# DVT-Notch-Filter.net
KiCad netlist of a schematic drawn in Altium Designer
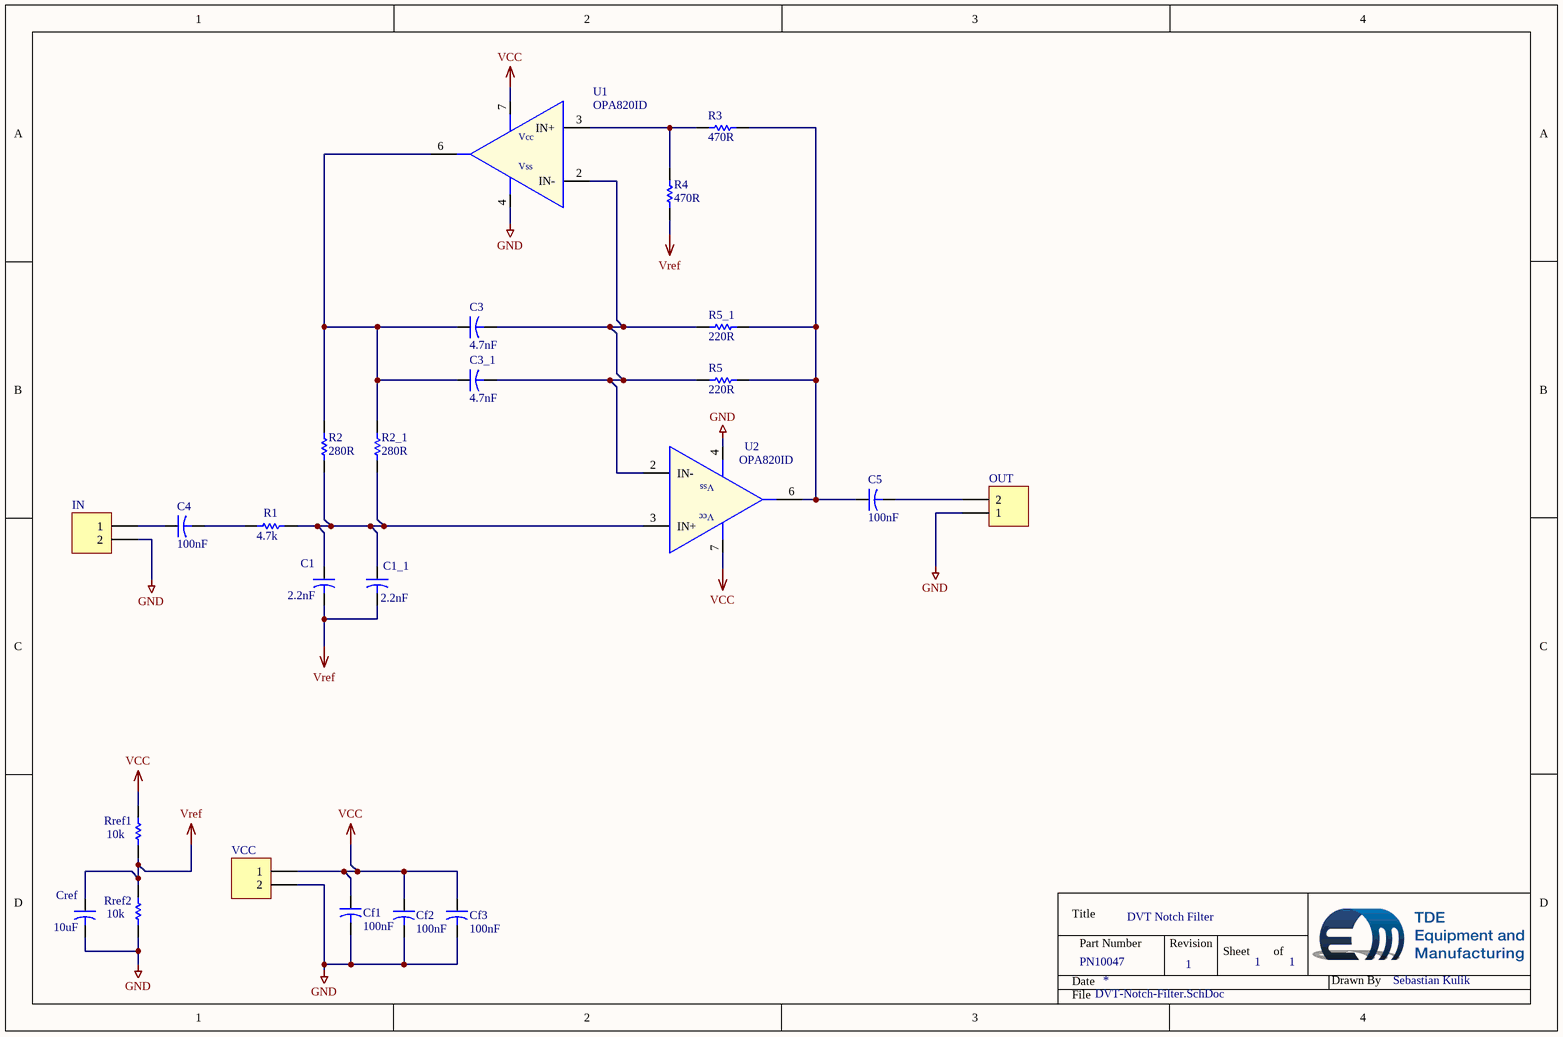
[diagram p0: DVT-Notch-Filter.SchDoc]

(export (version "E")
  (design (tool "Eeschema 10.0.6"))
  (components
    (comp (ref "*") (value "Eye") (footprint "Eye") (libsource (lib "ICs") (part "Eye")))
    (comp (ref "-") (value "Eye") (footprint "Eye") (libsource (lib "ICs") (part "Eye")))
    (comp (ref "C1")
      (value "2.2nF")
      (footprint "Dummy-10mm")
      (description "Capacitor-Dummy-THT")
      (fields (field (name "PUBLISHER") "Sebastian Kulik"))
      (libsource (lib "Capacitors") (part "Capacitor-Dummy-THT"))
    )
    (comp (ref "C1_1")
      (value "2.2nF")
      (footprint "Dummy-10mm")
      (description "Capacitor-Dummy-THT")
      (fields (field (name "PUBLISHER") "Sebastian Kulik"))
      (libsource (lib "Capacitors") (part "Capacitor-Dummy-THT"))
    )
    (comp (ref "C3")
      (value "4.7nF")
      (footprint "Dummy-10mm")
      (description "Capacitor-Dummy-THT")
      (fields (field (name "PUBLISHER") "Sebastian Kulik"))
      (libsource (lib "Capacitors") (part "Capacitor-Dummy-THT"))
    )
    (comp (ref "C3_1")
      (value "4.7nF")
      (footprint "Dummy-10mm")
      (description "Capacitor-Dummy-THT")
      (fields (field (name "PUBLISHER") "Sebastian Kulik"))
      (libsource (lib "Capacitors") (part "Capacitor-Dummy-THT"))
    )
    (comp (ref "C4")
      (value "100nF")
      (footprint "Dummy-10mm")
      (description "Capacitor-Dummy-THT")
      (fields (field (name "PUBLISHER") "Sebastian Kulik"))
      (libsource (lib "Capacitors") (part "Capacitor-Dummy-THT"))
    )
    (comp (ref "C5")
      (value "100nF")
      (footprint "Dummy-10mm")
      (description "Capacitor-Dummy-THT")
      (fields (field (name "PUBLISHER") "Sebastian Kulik"))
      (libsource (lib "Capacitors") (part "Capacitor-Dummy-THT"))
    )
    (comp (ref "Cf1")
      (value "100nF")
      (footprint "Dummy-10mm")
      (description "Capacitor-Dummy-THT")
      (fields (field (name "PUBLISHER") "Sebastian Kulik"))
      (libsource (lib "Capacitors") (part "Capacitor-Dummy-THT"))
    )
    (comp (ref "Cf2")
      (value "100nF")
      (footprint "Dummy-10mm")
      (description "Capacitor-Dummy-THT")
      (fields (field (name "PUBLISHER") "Sebastian Kulik"))
      (libsource (lib "Capacitors") (part "Capacitor-Dummy-THT"))
    )
    (comp (ref "Cf3")
      (value "100nF")
      (footprint "Dummy-10mm")
      (description "Capacitor-Dummy-THT")
      (fields (field (name "PUBLISHER") "Sebastian Kulik"))
      (libsource (lib "Capacitors") (part "Capacitor-Dummy-THT"))
    )
    (comp (ref "Cref")
      (value "10uF")
      (footprint "Dummy-10mm")
      (description "Capacitor-Dummy-THT")
      (fields (field (name "PUBLISHER") "Sebastian Kulik"))
      (libsource (lib "Capacitors") (part "Capacitor-Dummy-THT"))
    )
    (comp (ref "IN")
      (value "PHOENIX_1715721")
      (footprint "Phoenix-2-5_08")
      (description "Phoenix, 2 pol, 5.08mm, 22A, 715721")
      (fields (field (name "MANUFACTURER") "Phoenix") (field (name "PUBLISHER") "Sebastian Kulik"))
      (libsource (lib "Connectors") (part "2Pol_1715721"))
    )
    (comp (ref "OUT")
      (value "PHOENIX_1715721")
      (footprint "Phoenix-2-5_08")
      (description "Phoenix, 2 pol, 5.08mm, 22A, 715721")
      (fields (field (name "MANUFACTURER") "Phoenix") (field (name "PUBLISHER") "Sebastian Kulik"))
      (libsource (lib "") (part "2Pol_1715721_1"))
    )
    (comp (ref "R1")
      (value "4.7k")
      (footprint "Dummy-10mm")
      (description "Resistor-Dummy-THT")
      (fields (field (name "PUBLISHER") "Sebastian Kulik"))
      (libsource (lib "Resistors") (part "Resistor-Dummy-THT"))
    )
    (comp (ref "R2")
      (value "280R")
      (footprint "Dummy-10mm")
      (description "Resistor-Dummy-THT")
      (fields (field (name "PUBLISHER") "Sebastian Kulik"))
      (libsource (lib "Resistors") (part "Resistor-Dummy-THT"))
    )
    (comp (ref "R2_1")
      (value "280R")
      (footprint "Dummy-10mm")
      (description "Resistor-Dummy-THT")
      (fields (field (name "PUBLISHER") "Sebastian Kulik"))
      (libsource (lib "Resistors") (part "Resistor-Dummy-THT"))
    )
    (comp (ref "R3")
      (value "470R")
      (footprint "Dummy-10mm")
      (description "Resistor-Dummy-THT")
      (fields (field (name "PUBLISHER") "Sebastian Kulik"))
      (libsource (lib "Resistors") (part "Resistor-Dummy-THT"))
    )
    (comp (ref "R4")
      (value "470R")
      (footprint "Dummy-10mm")
      (description "Resistor-Dummy-THT")
      (fields (field (name "PUBLISHER") "Sebastian Kulik"))
      (libsource (lib "Resistors") (part "Resistor-Dummy-THT"))
    )
    (comp (ref "R5")
      (value "220R")
      (footprint "Dummy-10mm")
      (description "Resistor-Dummy-THT")
      (fields (field (name "PUBLISHER") "Sebastian Kulik"))
      (libsource (lib "Resistors") (part "Resistor-Dummy-THT"))
    )
    (comp (ref "R5_1")
      (value "220R")
      (footprint "Dummy-10mm")
      (description "Resistor-Dummy-THT")
      (fields (field (name "PUBLISHER") "Sebastian Kulik"))
      (libsource (lib "Resistors") (part "Resistor-Dummy-THT"))
    )
    (comp (ref "Rref1")
      (value "10k")
      (footprint "Dummy-10mm")
      (description "Resistor-Dummy-THT")
      (fields (field (name "PUBLISHER") "Sebastian Kulik"))
      (libsource (lib "Resistors") (part "Resistor-Dummy-THT"))
    )
    (comp (ref "Rref2")
      (value "10k")
      (footprint "Dummy-10mm")
      (description "Resistor-Dummy-THT")
      (fields (field (name "PUBLISHER") "Sebastian Kulik"))
      (libsource (lib "Resistors") (part "Resistor-Dummy-THT"))
    )
    (comp (ref "U1")
      (value "OPA820ID")
      (footprint "SOP8_L")
      (description "High speed OP, 260MHz")
      (fields (field (name "MANUFACTURER") "TI") (field (name "PUBLISHER") "Sebastian Kulik"))
      (libsource (lib "ICs") (part "OPA820ID"))
    )
    (comp (ref "U2")
      (value "OPA820ID")
      (footprint "SOP8_L")
      (description "High speed OP, 260MHz")
      (fields (field (name "MANUFACTURER") "TI") (field (name "PUBLISHER") "Sebastian Kulik"))
      (libsource (lib "") (part "OPA820ID_1"))
    )
    (comp (ref "VCC")
      (value "PHOENIX_1715721")
      (footprint "Phoenix-2-5_08")
      (description "Phoenix, 2 pol, 5.08mm, 22A, 715721")
      (fields (field (name "MANUFACTURER") "Phoenix") (field (name "PUBLISHER") "Sebastian Kulik"))
      (libsource (lib "Connectors") (part "2Pol_1715721"))
    )
  )
  (nets
    (net (code "1") (name "GND") (class "Default")
      (node (ref "Cf1") (pin "2") (pinfunction "2_2") (pintype "passive"))
      (node (ref "Cf2") (pin "2") (pinfunction "2_2") (pintype "passive"))
      (node (ref "Cf3") (pin "2") (pinfunction "2_2") (pintype "passive"))
      (node (ref "Cref") (pin "2") (pinfunction "2_2") (pintype "passive"))
      (node (ref "IN") (pin "2") (pinfunction "2_2") (pintype "passive"))
      (node (ref "OUT") (pin "1") (pinfunction "1_1") (pintype "passive"))
      (node (ref "Rref2") (pin "1") (pinfunction "1_1") (pintype "passive"))
      (node (ref "U1") (pin "4") (pinfunction "Vss_4") (pintype "passive"))
      (node (ref "U2") (pin "4") (pinfunction "Vss_4") (pintype "passive"))
      (node (ref "VCC") (pin "2") (pinfunction "2_2") (pintype "passive"))
    )
    (net (code "2") (name "Net-(C4-Pad1)") (class "Default")
      (node (ref "C4") (pin "1") (pinfunction "1_1") (pintype "passive"))
      (node (ref "IN") (pin "1") (pinfunction "1_1") (pintype "passive"))
    )
    (net (code "3") (name "Net-(C4-Pad2)") (class "Default")
      (node (ref "C4") (pin "2") (pinfunction "2_2") (pintype "passive"))
      (node (ref "R1") (pin "2") (pinfunction "2_2") (pintype "passive"))
    )
    (net (code "4") (name "Net-(C5-Pad2)") (class "Default")
      (node (ref "C5") (pin "2") (pinfunction "2_2") (pintype "passive"))
      (node (ref "OUT") (pin "2") (pinfunction "2_2") (pintype "passive"))
    )
    (net (code "5") (name "Net-(U1-IN+)") (class "Default")
      (node (ref "R3") (pin "2") (pinfunction "2_2") (pintype "passive"))
      (node (ref "R4") (pin "2") (pinfunction "2_2") (pintype "passive"))
      (node (ref "U1") (pin "3") (pinfunction "IN+_3") (pintype "power_in"))
    )
    (net (code "6") (name "Net-(U1-IN-)") (class "Default")
      (node (ref "C3") (pin "2") (pinfunction "2_2") (pintype "passive"))
      (node (ref "C3_1") (pin "2") (pinfunction "2_2") (pintype "passive"))
      (node (ref "R5") (pin "1") (pinfunction "1_1") (pintype "passive"))
      (node (ref "R5_1") (pin "1") (pinfunction "1_1") (pintype "passive"))
      (node (ref "U1") (pin "2") (pinfunction "IN-_2") (pintype "passive"))
      (node (ref "U2") (pin "2") (pinfunction "IN-_2") (pintype "passive"))
    )
    (net (code "7") (name "Net-(U1-OUT)") (class "Default")
      (node (ref "C3") (pin "1") (pinfunction "1_1") (pintype "passive"))
      (node (ref "C3_1") (pin "1") (pinfunction "1_1") (pintype "passive"))
      (node (ref "R2") (pin "1") (pinfunction "1_1") (pintype "passive"))
      (node (ref "R2_1") (pin "1") (pinfunction "1_1") (pintype "passive"))
      (node (ref "U1") (pin "6") (pinfunction "OUT_6") (pintype "passive"))
    )
    (net (code "8") (name "Net-(U2-IN+)") (class "Default")
      (node (ref "C1") (pin "1") (pinfunction "1_1") (pintype "passive"))
      (node (ref "C1_1") (pin "1") (pinfunction "1_1") (pintype "passive"))
      (node (ref "R1") (pin "1") (pinfunction "1_1") (pintype "passive"))
      (node (ref "R2") (pin "2") (pinfunction "2_2") (pintype "passive"))
      (node (ref "R2_1") (pin "2") (pinfunction "2_2") (pintype "passive"))
      (node (ref "U2") (pin "3") (pinfunction "IN+_3") (pintype "power_in"))
    )
    (net (code "9") (name "Net-(U2-OUT)") (class "Default")
      (node (ref "C5") (pin "1") (pinfunction "1_1") (pintype "passive"))
      (node (ref "R3") (pin "1") (pinfunction "1_1") (pintype "passive"))
      (node (ref "R5") (pin "2") (pinfunction "2_2") (pintype "passive"))
      (node (ref "R5_1") (pin "2") (pinfunction "2_2") (pintype "passive"))
      (node (ref "U2") (pin "6") (pinfunction "OUT_6") (pintype "passive"))
    )
    (net (code "10") (name "VCC") (class "Default")
      (node (ref "Cf1") (pin "1") (pinfunction "1_1") (pintype "passive"))
      (node (ref "Cf2") (pin "1") (pinfunction "1_1") (pintype "passive"))
      (node (ref "Cf3") (pin "1") (pinfunction "1_1") (pintype "passive"))
      (node (ref "Rref1") (pin "2") (pinfunction "2_2") (pintype "passive"))
      (node (ref "U1") (pin "7") (pinfunction "Vcc_7") (pintype "passive"))
      (node (ref "U2") (pin "7") (pinfunction "Vcc_7") (pintype "passive"))
      (node (ref "VCC") (pin "1") (pinfunction "1_1") (pintype "passive"))
    )
    (net (code "11") (name "Vref") (class "Default")
      (node (ref "C1") (pin "2") (pinfunction "2_2") (pintype "passive"))
      (node (ref "C1_1") (pin "2") (pinfunction "2_2") (pintype "passive"))
      (node (ref "Cref") (pin "1") (pinfunction "1_1") (pintype "passive"))
      (node (ref "R4") (pin "1") (pinfunction "1_1") (pintype "passive"))
      (node (ref "Rref1") (pin "1") (pinfunction "1_1") (pintype "passive"))
      (node (ref "Rref2") (pin "2") (pinfunction "2_2") (pintype "passive"))
    )
  )
)
